# DasAltimeter_v1_1.net
KiCad netlist of a schematic drawn in EAGLE
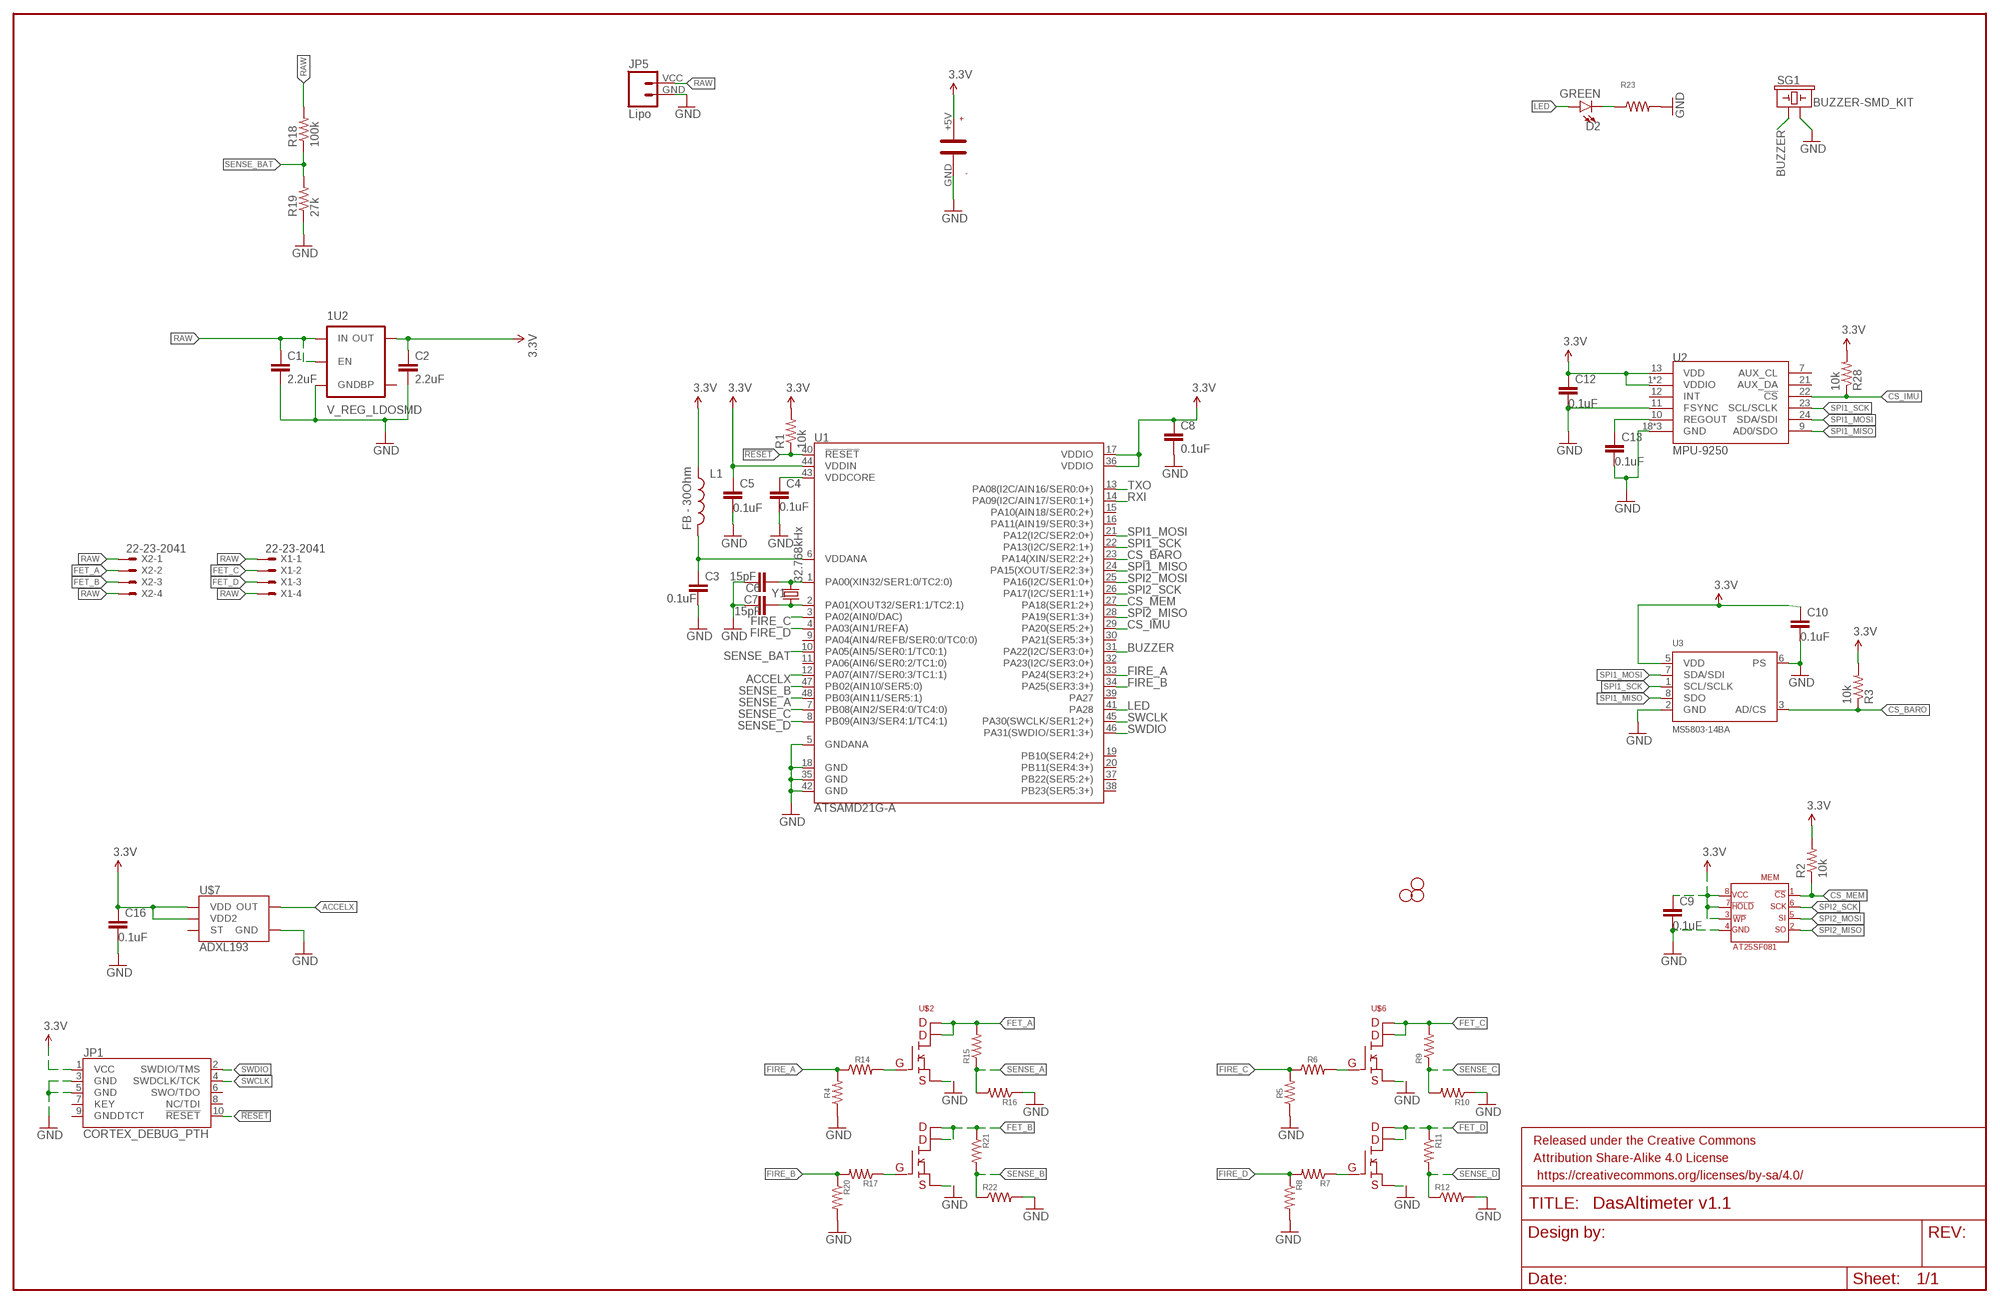
[diagram p0: schematic, sheet 1]

(export (version "E")
  (design (tool "Eeschema 10.0.6"))
  (components
    (comp (ref "1U2")
      (value "V_REG_LDOSMD")
      (footprint "eagle-import:SOT23-5")
      (libsource (lib "eagle-import") (part "V_REG_LDOSMD"))
    )
    (comp (ref "C1")
      (value "2.2uF")
      (footprint "eagle-import:0603-CAP")
      (libsource (lib "eagle-import") (part "CAP0603-CAP"))
    )
    (comp (ref "C2")
      (value "2.2uF")
      (footprint "eagle-import:0603-CAP")
      (libsource (lib "eagle-import") (part "CAP0603-CAP"))
    )
    (comp (ref "C3")
      (value "0.1uF")
      (footprint "eagle-import:0402-CAP")
      (libsource (lib "eagle-import") (part "SparkFun-Passives_CAP0402-CAP"))
    )
    (comp (ref "C4")
      (value "0.1uF")
      (footprint "eagle-import:0402-CAP")
      (libsource (lib "eagle-import") (part "SparkFun-Passives_CAP0402-CAP"))
    )
    (comp (ref "C5")
      (value "0.1uF")
      (footprint "eagle-import:0402-CAP")
      (libsource (lib "eagle-import") (part "SparkFun-Passives_CAP0402-CAP"))
    )
    (comp (ref "C6")
      (value "15pF")
      (footprint "eagle-import:0402-CAP")
      (libsource (lib "eagle-import") (part "SparkFun-Passives_CAP0402-CAP"))
    )
    (comp (ref "C7")
      (value "15pF")
      (footprint "eagle-import:0402-CAP")
      (libsource (lib "eagle-import") (part "SparkFun-Passives_CAP0402-CAP"))
    )
    (comp (ref "C8")
      (value "0.1uF")
      (footprint "eagle-import:0402-CAP")
      (libsource (lib "eagle-import") (part "SparkFun-Passives_CAP0402-CAP"))
    )
    (comp (ref "C9")
      (value "0.1uF")
      (footprint "eagle-import:0402-CAP")
      (libsource (lib "eagle-import") (part "SparkFun-Passives_CAP0402-CAP"))
    )
    (comp (ref "C10")
      (value "0.1uF")
      (footprint "eagle-import:0402-CAP")
      (libsource (lib "eagle-import") (part "SparkFun-Passives_CAP0402-CAP"))
    )
    (comp (ref "C12")
      (value "0.1uF")
      (footprint "eagle-import:0402-CAP")
      (libsource (lib "eagle-import") (part "SparkFun-Passives_CAP0402-CAP"))
    )
    (comp (ref "C13")
      (value "0.1uF")
      (footprint "eagle-import:0402-CAP")
      (libsource (lib "eagle-import") (part "SparkFun-Passives_CAP0402-CAP"))
    )
    (comp (ref "C16")
      (value "0.1uF")
      (footprint "eagle-import:0402-CAP")
      (libsource (lib "eagle-import") (part "SparkFun-Passives_CAP0402-CAP"))
    )
    (comp (ref "D2")
      (value "GREEN")
      (footprint "eagle-import:LED-1206")
      (libsource (lib "eagle-import") (part "LED-GREEN1206"))
    )
    (comp (ref "FRAME1")
      (value "FRAME-LEDGER")
      (footprint "eagle-import:CREATIVE_COMMONS")
      (libsource (lib "eagle-import") (part "FRAME-LEDGER"))
    )
    (comp (ref "JP1")
      (value "CORTEX_DEBUG_PTH")
      (footprint "eagle-import:2X5-PTH-1.27MM")
      (libsource (lib "eagle-import") (part "CORTEX_DEBUG_PTH"))
    )
    (comp (ref "JP5")
      (value "Lipo")
      (footprint "eagle-import:JST-2-SMD-VERT")
      (libsource (lib "eagle-import") (part "M024UCON-15767"))
    )
    (comp (ref "L1")
      (value "FB - 30Ohm")
      (footprint "eagle-import:0603")
      (libsource (lib "eagle-import") (part "INDUCTOR0603"))
    )
    (comp (ref "MEM")
      (value "AT25SF081")
      (footprint "eagle-import:AT25SF081")
      (libsource (lib "eagle-import") (part "AT25SF081"))
    )
    (comp (ref "R1")
      (value "10k")
      (footprint "eagle-import:0402-RES")
      (libsource (lib "eagle-import") (part "RESISTOR0402-RES"))
    )
    (comp (ref "R2")
      (value "10k")
      (footprint "eagle-import:0402-RES")
      (libsource (lib "eagle-import") (part "RESISTOR0402-RES"))
    )
    (comp (ref "R3")
      (value "10k")
      (footprint "eagle-import:0402-RES")
      (libsource (lib "eagle-import") (part "RESISTOR0402-RES"))
    )
    (comp (ref "R4")
      (value "RESISTOR0402")
      (footprint "eagle-import:0402")
      (libsource (lib "eagle-import") (part "RESISTOR0402"))
    )
    (comp (ref "R5")
      (value "RESISTOR0402")
      (footprint "eagle-import:0402")
      (libsource (lib "eagle-import") (part "RESISTOR0402"))
    )
    (comp (ref "R6")
      (value "RESISTOR0402")
      (footprint "eagle-import:0402")
      (libsource (lib "eagle-import") (part "RESISTOR0402"))
    )
    (comp (ref "R7")
      (value "RESISTOR0402")
      (footprint "eagle-import:0402")
      (libsource (lib "eagle-import") (part "RESISTOR0402"))
    )
    (comp (ref "R8")
      (value "RESISTOR0402")
      (footprint "eagle-import:0402")
      (libsource (lib "eagle-import") (part "RESISTOR0402"))
    )
    (comp (ref "R9")
      (value "RESISTOR0402")
      (footprint "eagle-import:0402")
      (libsource (lib "eagle-import") (part "RESISTOR0402"))
    )
    (comp (ref "R10")
      (value "RESISTOR0402")
      (footprint "eagle-import:0402")
      (libsource (lib "eagle-import") (part "RESISTOR0402"))
    )
    (comp (ref "R11")
      (value "RESISTOR0402")
      (footprint "eagle-import:0402")
      (libsource (lib "eagle-import") (part "RESISTOR0402"))
    )
    (comp (ref "R12")
      (value "RESISTOR0402")
      (footprint "eagle-import:0402")
      (libsource (lib "eagle-import") (part "RESISTOR0402"))
    )
    (comp (ref "R14")
      (value "RESISTOR0402")
      (footprint "eagle-import:0402")
      (libsource (lib "eagle-import") (part "RESISTOR0402"))
    )
    (comp (ref "R15")
      (value "RESISTOR0402")
      (footprint "eagle-import:0402")
      (libsource (lib "eagle-import") (part "RESISTOR0402"))
    )
    (comp (ref "R16")
      (value "RESISTOR0402")
      (footprint "eagle-import:0402")
      (libsource (lib "eagle-import") (part "RESISTOR0402"))
    )
    (comp (ref "R17")
      (value "RESISTOR0402")
      (footprint "eagle-import:0402")
      (libsource (lib "eagle-import") (part "RESISTOR0402"))
    )
    (comp (ref "R18")
      (value "100k")
      (footprint "eagle-import:0402-RES")
      (libsource (lib "eagle-import") (part "RESISTOR0402-RES"))
    )
    (comp (ref "R19")
      (value "27k")
      (footprint "eagle-import:0402-RES")
      (libsource (lib "eagle-import") (part "RESISTOR0402-RES"))
    )
    (comp (ref "R20")
      (value "RESISTOR0402")
      (footprint "eagle-import:0402")
      (libsource (lib "eagle-import") (part "RESISTOR0402"))
    )
    (comp (ref "R21")
      (value "RESISTOR0402")
      (footprint "eagle-import:0402")
      (libsource (lib "eagle-import") (part "RESISTOR0402"))
    )
    (comp (ref "R22")
      (value "RESISTOR0402")
      (footprint "eagle-import:0402")
      (libsource (lib "eagle-import") (part "RESISTOR0402"))
    )
    (comp (ref "R23")
      (value "RESISTOR0402")
      (footprint "eagle-import:0402")
      (libsource (lib "eagle-import") (part "RESISTOR0402"))
    )
    (comp (ref "R28")
      (value "10k")
      (footprint "eagle-import:0402-RES")
      (libsource (lib "eagle-import") (part "RESISTOR0402-RES"))
    )
    (comp (ref "SG1")
      (value "BUZZER-SMD_KIT")
      (footprint "eagle-import:BUZZER-CCV-KIT")
      (libsource (lib "eagle-import") (part "BUZZER-SMD_KIT"))
    )
    (comp (ref "STANDOFF2")
      (value "STAND-OFF")
      (footprint "eagle-import:STAND-OFF")
      (libsource (lib "eagle-import") (part "STAND-OFF"))
    )
    (comp (ref "STANDOFF3")
      (value "STAND-OFF")
      (footprint "eagle-import:STAND-OFF")
      (libsource (lib "eagle-import") (part "STAND-OFF"))
    )
    (comp (ref "STANDOFF4")
      (value "STAND-OFF")
      (footprint "eagle-import:STAND-OFF")
      (libsource (lib "eagle-import") (part "STAND-OFF"))
    )
    (comp (ref "U$1")
      (value "PB-5R0H104-R")
      (footprint "eagle-import:PB-5R0H104-R")
      (libsource (lib "eagle-import") (part "PB-5R0H104-R"))
    )
    (comp (ref "U$2")
      (value "SI7232DN")
      (footprint "eagle-import:SI7232DN")
      (libsource (lib "eagle-import") (part "SI7232DN"))
    )
    (comp (ref "U$6")
      (value "SI7232DN")
      (footprint "eagle-import:SI7232DN")
      (libsource (lib "eagle-import") (part "SI7232DN"))
    )
    (comp (ref "U$7")
      (value "ADXL193")
      (footprint "eagle-import:LCC-8")
      (libsource (lib "eagle-import") (part "ADXL193"))
    )
    (comp (ref "U1")
      (value "ATSAMD21G-A")
      (footprint "eagle-import:TQFP-48")
      (libsource (lib "eagle-import") (part "ATSAMD21G-A"))
    )
    (comp (ref "U2")
      (value "MPU-9250")
      (footprint "eagle-import:QFN24_PAD")
      (libsource (lib "eagle-import") (part "MPU-9250"))
    )
    (comp (ref "U3")
      (value "MS5803-14BA")
      (footprint "eagle-import:MS5803")
      (libsource (lib "eagle-import") (part "MS5803-14BA"))
    )
    (comp (ref "X1")
      (value "22-23-2041")
      (footprint "eagle-import:22-23-2041")
      (fields (field (name "MF") "MOLEX"))
      (libsource (lib "eagle-import") (part "22-23-2041"))
    )
    (comp (ref "X2")
      (value "22-23-2041")
      (footprint "eagle-import:22-23-2041")
      (fields (field (name "MF") "MOLEX"))
      (libsource (lib "eagle-import") (part "22-23-2041"))
    )
    (comp (ref "Y1")
      (value "32.768kHx")
      (footprint "eagle-import:CRYSTAL-SMD-3.2X1.5MM")
      (libsource (lib "eagle-import") (part "CRYSTAL3.2X1.5MM"))
    )
  )
  (nets
    (net (code "1") (name "/BUZZER") (class "Default")
      (node (ref "SG1") (pin "+") (pinfunction "1_+") (pintype "passive"))
      (node (ref "U1") (pin "31") (pinfunction "PA22(I2C/SER3:0+)_31") (pintype "bidirectional"))
    )
    (net (code "2") (name "/RXI") (class "Default")
      (node (ref "U1") (pin "14") (pinfunction "PA09(I2C/AIN17/SER0:1+)_14") (pintype "bidirectional"))
    )
    (net (code "3") (name "/TXO") (class "Default")
      (node (ref "U1") (pin "13") (pinfunction "PA08(I2C/AIN16/SER0:0+)_13") (pintype "bidirectional"))
    )
    (net (code "4") (name "/~{RESET}") (class "Default")
      (node (ref "JP1") (pin "10") (pinfunction "~{RESET}_10") (pintype "bidirectional"))
      (node (ref "R1") (pin "1") (pinfunction "1_1") (pintype "passive"))
      (node (ref "U1") (pin "40") (pinfunction "~{RESET}_40") (pintype "bidirectional"))
    )
    (net (code "5") (name "3.3V") (class "Default")
      (node (ref "1U2") (pin "5") (pinfunction "OUT_5") (pintype "passive"))
      (node (ref "C10") (pin "1") (pinfunction "1_1") (pintype "passive"))
      (node (ref "C12") (pin "1") (pinfunction "1_1") (pintype "passive"))
      (node (ref "C16") (pin "1") (pinfunction "1_1") (pintype "passive"))
      (node (ref "C2") (pin "1") (pinfunction "1_1") (pintype "passive"))
      (node (ref "C5") (pin "1") (pinfunction "1_1") (pintype "passive"))
      (node (ref "C8") (pin "1") (pinfunction "1_1") (pintype "passive"))
      (node (ref "C9") (pin "1") (pinfunction "1_1") (pintype "passive"))
      (node (ref "JP1") (pin "1") (pinfunction "VCC_1") (pintype "bidirectional"))
      (node (ref "L1") (pin "1") (pinfunction "1_1") (pintype "passive"))
      (node (ref "MEM") (pin "!HOLD") (pinfunction "~{HOLD}_!HOLD") (pintype "bidirectional"))
      (node (ref "MEM") (pin "!WP") (pinfunction "~{WP}_!WP") (pintype "bidirectional"))
      (node (ref "MEM") (pin "VCC") (pinfunction "VCC_VCC") (pintype "bidirectional"))
      (node (ref "R1") (pin "2") (pinfunction "2_2") (pintype "passive"))
      (node (ref "R2") (pin "2") (pinfunction "2_2") (pintype "passive"))
      (node (ref "R28") (pin "2") (pinfunction "2_2") (pintype "passive"))
      (node (ref "R3") (pin "2") (pinfunction "2_2") (pintype "passive"))
      (node (ref "U$1") (pin "+5V") (pinfunction "+5V_+5V") (pintype "bidirectional"))
      (node (ref "U$7") (pin "P$7") (pinfunction "VDD_P$7") (pintype "bidirectional"))
      (node (ref "U$7") (pin "P$8") (pinfunction "VDD2_P$8") (pintype "bidirectional"))
      (node (ref "U1") (pin "17") (pinfunction "VDDIO_17") (pintype "bidirectional"))
      (node (ref "U1") (pin "36") (pinfunction "VDDIO_36") (pintype "bidirectional"))
      (node (ref "U1") (pin "44") (pinfunction "VDDIN_44") (pintype "bidirectional"))
      (node (ref "U2") (pin "1") (pinfunction "VDDIO_1") (pintype "bidirectional"))
      (node (ref "U2") (pin "13") (pinfunction "VDD_13") (pintype "bidirectional"))
      (node (ref "U2") (pin "8") (pinfunction "VDDIO_8") (pintype "bidirectional"))
      (node (ref "U3") (pin "5") (pinfunction "VDD_5") (pintype "bidirectional"))
    )
    (net (code "6") (name "ACCELX") (class "Default")
      (node (ref "U$7") (pin "P$6") (pinfunction "OUT_P$6") (pintype "bidirectional"))
      (node (ref "U1") (pin "12") (pinfunction "PA07(AIN7/SER0:3/TC1:1)_12") (pintype "bidirectional"))
    )
    (net (code "7") (name "CS_BARO") (class "Default")
      (node (ref "R3") (pin "1") (pinfunction "1_1") (pintype "passive"))
      (node (ref "U1") (pin "23") (pinfunction "PA14(XIN/SER2:2+)_23") (pintype "bidirectional"))
      (node (ref "U3") (pin "3") (pinfunction "AD/CS_3") (pintype "bidirectional"))
    )
    (net (code "8") (name "CS_IMU") (class "Default")
      (node (ref "R28") (pin "1") (pinfunction "1_1") (pintype "passive"))
      (node (ref "U1") (pin "29") (pinfunction "PA20(SER5:2+)_29") (pintype "bidirectional"))
      (node (ref "U2") (pin "22") (pinfunction "~{CS}_22") (pintype "bidirectional"))
    )
    (net (code "9") (name "CS_MEM") (class "Default")
      (node (ref "MEM") (pin "!CS") (pinfunction "~{CS}_!CS") (pintype "bidirectional"))
      (node (ref "R2") (pin "1") (pinfunction "1_1") (pintype "passive"))
      (node (ref "U1") (pin "27") (pinfunction "PA18(SER1:2+)_27") (pintype "bidirectional"))
    )
    (net (code "10") (name "FET_A") (class "Default")
      (node (ref "R15") (pin "2") (pinfunction "2_2") (pintype "passive"))
      (node (ref "U$2") (pin "7") (pinfunction "PIN7_7") (pintype "bidirectional"))
      (node (ref "U$2") (pin "8") (pinfunction "PIN8_8") (pintype "bidirectional"))
      (node (ref "X2") (pin "2") (pinfunction "S_2") (pintype "passive"))
    )
    (net (code "11") (name "FET_B") (class "Default")
      (node (ref "R21") (pin "1") (pinfunction "1_1") (pintype "passive"))
      (node (ref "U$2") (pin "5") (pinfunction "PIN5_5") (pintype "bidirectional"))
      (node (ref "U$2") (pin "6") (pinfunction "PIN6_6") (pintype "bidirectional"))
      (node (ref "X2") (pin "3") (pinfunction "S_3") (pintype "passive"))
    )
    (net (code "12") (name "FET_C") (class "Default")
      (node (ref "R9") (pin "2") (pinfunction "2_2") (pintype "passive"))
      (node (ref "U$6") (pin "7") (pinfunction "PIN7_7") (pintype "bidirectional"))
      (node (ref "U$6") (pin "8") (pinfunction "PIN8_8") (pintype "bidirectional"))
      (node (ref "X1") (pin "2") (pinfunction "S_2") (pintype "passive"))
    )
    (net (code "13") (name "FET_D") (class "Default")
      (node (ref "R11") (pin "1") (pinfunction "1_1") (pintype "passive"))
      (node (ref "U$6") (pin "5") (pinfunction "PIN5_5") (pintype "bidirectional"))
      (node (ref "U$6") (pin "6") (pinfunction "PIN6_6") (pintype "bidirectional"))
      (node (ref "X1") (pin "3") (pinfunction "S_3") (pintype "passive"))
    )
    (net (code "14") (name "FIRE_A") (class "Default")
      (node (ref "R14") (pin "1") (pinfunction "1_1") (pintype "passive"))
      (node (ref "R4") (pin "2") (pinfunction "2_2") (pintype "passive"))
      (node (ref "U1") (pin "33") (pinfunction "PA24(SER3:2+)_33") (pintype "bidirectional"))
    )
    (net (code "15") (name "FIRE_B") (class "Default")
      (node (ref "R17") (pin "2") (pinfunction "2_2") (pintype "passive"))
      (node (ref "R20") (pin "1") (pinfunction "1_1") (pintype "passive"))
      (node (ref "U1") (pin "34") (pinfunction "PA25(SER3:3+)_34") (pintype "bidirectional"))
    )
    (net (code "16") (name "FIRE_C") (class "Default")
      (node (ref "R5") (pin "2") (pinfunction "2_2") (pintype "passive"))
      (node (ref "R6") (pin "1") (pinfunction "1_1") (pintype "passive"))
      (node (ref "U1") (pin "3") (pinfunction "PA02(AIN0/DAC)_3") (pintype "bidirectional"))
    )
    (net (code "17") (name "FIRE_D") (class "Default")
      (node (ref "R7") (pin "2") (pinfunction "2_2") (pintype "passive"))
      (node (ref "R8") (pin "1") (pinfunction "1_1") (pintype "passive"))
      (node (ref "U1") (pin "4") (pinfunction "PA03(AIN1/REFA)_4") (pintype "bidirectional"))
    )
    (net (code "18") (name "GND") (class "Default")
      (node (ref "1U2") (pin "2") (pinfunction "GND_2") (pintype "input"))
      (node (ref "C1") (pin "2") (pinfunction "2_2") (pintype "passive"))
      (node (ref "C10") (pin "2") (pinfunction "2_2") (pintype "passive"))
      (node (ref "C12") (pin "2") (pinfunction "2_2") (pintype "passive"))
      (node (ref "C13") (pin "2") (pinfunction "2_2") (pintype "passive"))
      (node (ref "C16") (pin "2") (pinfunction "2_2") (pintype "passive"))
      (node (ref "C2") (pin "2") (pinfunction "2_2") (pintype "passive"))
      (node (ref "C3") (pin "2") (pinfunction "2_2") (pintype "passive"))
      (node (ref "C4") (pin "2") (pinfunction "2_2") (pintype "passive"))
      (node (ref "C5") (pin "2") (pinfunction "2_2") (pintype "passive"))
      (node (ref "C6") (pin "2") (pinfunction "2_2") (pintype "passive"))
      (node (ref "C7") (pin "2") (pinfunction "2_2") (pintype "passive"))
      (node (ref "C8") (pin "2") (pinfunction "2_2") (pintype "passive"))
      (node (ref "C9") (pin "2") (pinfunction "2_2") (pintype "passive"))
      (node (ref "JP1") (pin "3") (pinfunction "GND_3") (pintype "bidirectional"))
      (node (ref "JP1") (pin "5") (pinfunction "GND_5") (pintype "bidirectional"))
      (node (ref "JP5") (pin "GND") (pinfunction "1_GND") (pintype "passive"))
      (node (ref "MEM") (pin "GND") (pinfunction "GND_GND") (pintype "bidirectional"))
      (node (ref "R10") (pin "1") (pinfunction "1_1") (pintype "passive"))
      (node (ref "R12") (pin "2") (pinfunction "2_2") (pintype "passive"))
      (node (ref "R16") (pin "1") (pinfunction "1_1") (pintype "passive"))
      (node (ref "R19") (pin "1") (pinfunction "1_1") (pintype "passive"))
      (node (ref "R20") (pin "2") (pinfunction "2_2") (pintype "passive"))
      (node (ref "R22") (pin "2") (pinfunction "2_2") (pintype "passive"))
      (node (ref "R23") (pin "2") (pinfunction "2_2") (pintype "passive"))
      (node (ref "R4") (pin "1") (pinfunction "1_1") (pintype "passive"))
      (node (ref "R5") (pin "1") (pinfunction "1_1") (pintype "passive"))
      (node (ref "R8") (pin "2") (pinfunction "2_2") (pintype "passive"))
      (node (ref "SG1") (pin "-") (pinfunction "2_-") (pintype "passive"))
      (node (ref "U$1") (pin "GND") (pinfunction "GND_GND") (pintype "bidirectional"))
      (node (ref "U$2") (pin "1") (pinfunction "PIN1_1") (pintype "bidirectional"))
      (node (ref "U$2") (pin "3") (pinfunction "PIN3_3") (pintype "bidirectional"))
      (node (ref "U$6") (pin "1") (pinfunction "PIN1_1") (pintype "bidirectional"))
      (node (ref "U$6") (pin "3") (pinfunction "PIN3_3") (pintype "bidirectional"))
      (node (ref "U$7") (pin "P$3") (pinfunction "GND_P$3") (pintype "bidirectional"))
      (node (ref "U1") (pin "18") (pinfunction "GND_18") (pintype "bidirectional"))
      (node (ref "U1") (pin "35") (pinfunction "GND_35") (pintype "bidirectional"))
      (node (ref "U1") (pin "42") (pinfunction "GND_42") (pintype "bidirectional"))
      (node (ref "U1") (pin "5") (pinfunction "GNDANA_5") (pintype "bidirectional"))
      (node (ref "U2") (pin "11") (pinfunction "FSYNC_11") (pintype "bidirectional"))
      (node (ref "U2") (pin "18") (pinfunction "GND_18") (pintype "bidirectional"))
      (node (ref "U2") (pin "20") (pinfunction "GND_20") (pintype "bidirectional"))
      (node (ref "U2") (pin "CENTER") (pinfunction "GND_CENTER") (pintype "bidirectional"))
      (node (ref "U3") (pin "2") (pinfunction "GND_2") (pintype "bidirectional"))
      (node (ref "U3") (pin "6") (pinfunction "PS_6") (pintype "bidirectional"))
    )
    (net (code "19") (name "LED") (class "Default")
      (node (ref "D2") (pin "A") (pinfunction "A_A") (pintype "passive"))
      (node (ref "U1") (pin "41") (pinfunction "PA28_41") (pintype "bidirectional"))
    )
    (net (code "20") (name "Net-(D2-PadC)") (class "Default")
      (node (ref "D2") (pin "C") (pinfunction "C_C") (pintype "passive"))
      (node (ref "R23") (pin "1") (pinfunction "1_1") (pintype "passive"))
    )
    (net (code "21") (name "Net-(U$2-PIN2)") (class "Default")
      (node (ref "R14") (pin "2") (pinfunction "2_2") (pintype "passive"))
      (node (ref "U$2") (pin "2") (pinfunction "PIN2_2") (pintype "bidirectional"))
    )
    (net (code "22") (name "Net-(U$2-PIN4)") (class "Default")
      (node (ref "R17") (pin "1") (pinfunction "1_1") (pintype "passive"))
      (node (ref "U$2") (pin "4") (pinfunction "PIN4_4") (pintype "bidirectional"))
    )
    (net (code "23") (name "Net-(U$6-PIN2)") (class "Default")
      (node (ref "R6") (pin "2") (pinfunction "2_2") (pintype "passive"))
      (node (ref "U$6") (pin "2") (pinfunction "PIN2_2") (pintype "bidirectional"))
    )
    (net (code "24") (name "Net-(U$6-PIN4)") (class "Default")
      (node (ref "R7") (pin "1") (pinfunction "1_1") (pintype "passive"))
      (node (ref "U$6") (pin "4") (pinfunction "PIN4_4") (pintype "bidirectional"))
    )
    (net (code "25") (name "Net-(U1-PA00(XIN32{slash}SER1:0{slash}TC2:0))") (class "Default")
      (node (ref "C6") (pin "1") (pinfunction "1_1") (pintype "passive"))
      (node (ref "U1") (pin "1") (pinfunction "PA00(XIN32/SER1:0/TC2:0)_1") (pintype "bidirectional"))
      (node (ref "Y1") (pin "P$2") (pinfunction "2_P$2") (pintype "passive"))
    )
    (net (code "26") (name "Net-(U1-PA01(XOUT32{slash}SER1:1{slash}TC2:1))") (class "Default")
      (node (ref "C7") (pin "1") (pinfunction "1_1") (pintype "passive"))
      (node (ref "U1") (pin "2") (pinfunction "PA01(XOUT32/SER1:1/TC2:1)_2") (pintype "bidirectional"))
      (node (ref "Y1") (pin "P$1") (pinfunction "1_P$1") (pintype "passive"))
    )
    (net (code "27") (name "Net-(U1-VDDANA)") (class "Default")
      (node (ref "C3") (pin "1") (pinfunction "1_1") (pintype "passive"))
      (node (ref "L1") (pin "2") (pinfunction "2_2") (pintype "passive"))
      (node (ref "U1") (pin "6") (pinfunction "VDDANA_6") (pintype "bidirectional"))
    )
    (net (code "28") (name "Net-(U1-VDDCORE)") (class "Default")
      (node (ref "C4") (pin "1") (pinfunction "1_1") (pintype "passive"))
      (node (ref "U1") (pin "43") (pinfunction "VDDCORE_43") (pintype "bidirectional"))
    )
    (net (code "29") (name "Net-(U2-REGOUT)") (class "Default")
      (node (ref "C13") (pin "1") (pinfunction "1_1") (pintype "passive"))
      (node (ref "U2") (pin "10") (pinfunction "REGOUT_10") (pintype "bidirectional"))
    )
    (net (code "30") (name "RAW") (class "Default")
      (node (ref "1U2") (pin "1") (pinfunction "IN_1") (pintype "input"))
      (node (ref "1U2") (pin "3") (pinfunction "EN_3") (pintype "input"))
      (node (ref "C1") (pin "1") (pinfunction "1_1") (pintype "passive"))
      (node (ref "JP5") (pin "VCC") (pinfunction "2_VCC") (pintype "passive"))
      (node (ref "R18") (pin "2") (pinfunction "2_2") (pintype "passive"))
      (node (ref "X1") (pin "1") (pinfunction "S_1") (pintype "passive"))
      (node (ref "X1") (pin "4") (pinfunction "S_4") (pintype "passive"))
      (node (ref "X2") (pin "1") (pinfunction "S_1") (pintype "passive"))
      (node (ref "X2") (pin "4") (pinfunction "S_4") (pintype "passive"))
    )
    (net (code "31") (name "SENSE_A") (class "Default")
      (node (ref "R15") (pin "1") (pinfunction "1_1") (pintype "passive"))
      (node (ref "R16") (pin "2") (pinfunction "2_2") (pintype "passive"))
      (node (ref "U1") (pin "48") (pinfunction "PB03(AIN11/SER5:1)_48") (pintype "bidirectional"))
    )
    (net (code "32") (name "SENSE_B") (class "Default")
      (node (ref "R21") (pin "2") (pinfunction "2_2") (pintype "passive"))
      (node (ref "R22") (pin "1") (pinfunction "1_1") (pintype "passive"))
      (node (ref "U1") (pin "47") (pinfunction "PB02(AIN10/SER5:0)_47") (pintype "bidirectional"))
    )
    (net (code "33") (name "SENSE_BAT") (class "Default")
      (node (ref "R18") (pin "1") (pinfunction "1_1") (pintype "passive"))
      (node (ref "R19") (pin "2") (pinfunction "2_2") (pintype "passive"))
      (node (ref "U1") (pin "10") (pinfunction "PA05(AIN5/SER0:1/TC0:1)_10") (pintype "bidirectional"))
    )
    (net (code "34") (name "SENSE_C") (class "Default")
      (node (ref "R10") (pin "2") (pinfunction "2_2") (pintype "passive"))
      (node (ref "R9") (pin "1") (pinfunction "1_1") (pintype "passive"))
      (node (ref "U1") (pin "7") (pinfunction "PB08(AIN2/SER4:0/TC4:0)_7") (pintype "bidirectional"))
    )
    (net (code "35") (name "SENSE_D") (class "Default")
      (node (ref "R11") (pin "2") (pinfunction "2_2") (pintype "passive"))
      (node (ref "R12") (pin "1") (pinfunction "1_1") (pintype "passive"))
      (node (ref "U1") (pin "8") (pinfunction "PB09(AIN3/SER4:1/TC4:1)_8") (pintype "bidirectional"))
    )
    (net (code "36") (name "SPI1_MISO") (class "Default")
      (node (ref "U1") (pin "24") (pinfunction "PA15(XOUT/SER2:3+)_24") (pintype "bidirectional"))
      (node (ref "U2") (pin "9") (pinfunction "AD0/SDO_9") (pintype "bidirectional"))
      (node (ref "U3") (pin "8") (pinfunction "SDO_8") (pintype "bidirectional"))
    )
    (net (code "37") (name "SPI1_MOSI") (class "Default")
      (node (ref "U1") (pin "21") (pinfunction "PA12(I2C/SER2:0+)_21") (pintype "bidirectional"))
      (node (ref "U2") (pin "24") (pinfunction "SDA/SDI_24") (pintype "bidirectional"))
      (node (ref "U3") (pin "7") (pinfunction "SDA/SDI_7") (pintype "bidirectional"))
    )
    (net (code "38") (name "SPI1_SCK") (class "Default")
      (node (ref "U1") (pin "22") (pinfunction "PA13(I2C/SER2:1+)_22") (pintype "bidirectional"))
      (node (ref "U2") (pin "23") (pinfunction "SCL/SCLK_23") (pintype "bidirectional"))
      (node (ref "U3") (pin "1") (pinfunction "SCL/SCLK_1") (pintype "bidirectional"))
    )
    (net (code "39") (name "SPI2_MISO") (class "Default")
      (node (ref "MEM") (pin "SO") (pinfunction "SO_SO") (pintype "bidirectional"))
      (node (ref "U1") (pin "28") (pinfunction "PA19(SER1:3+)_28") (pintype "bidirectional"))
    )
    (net (code "40") (name "SPI2_MOSI") (class "Default")
      (node (ref "MEM") (pin "SI") (pinfunction "SI_SI") (pintype "bidirectional"))
      (node (ref "U1") (pin "25") (pinfunction "PA16(I2C/SER1:0+)_25") (pintype "bidirectional"))
    )
    (net (code "41") (name "SPI2_SCK") (class "Default")
      (node (ref "MEM") (pin "SCK") (pinfunction "SCK_SCK") (pintype "bidirectional"))
      (node (ref "U1") (pin "26") (pinfunction "PA17(I2C/SER1:1+)_26") (pintype "bidirectional"))
    )
    (net (code "42") (name "SWCLK") (class "Default")
      (node (ref "JP1") (pin "4") (pinfunction "SWDCLK/TCK_4") (pintype "bidirectional"))
      (node (ref "U1") (pin "45") (pinfunction "PA30(SWCLK/SER1:2+)_45") (pintype "bidirectional"))
    )
    (net (code "43") (name "SWDIO") (class "Default")
      (node (ref "JP1") (pin "2") (pinfunction "SWDIO/TMS_2") (pintype "bidirectional"))
      (node (ref "U1") (pin "46") (pinfunction "PA31(SWDIO/SER1:3+)_46") (pintype "bidirectional"))
    )
    (net (code "44") (name "unconnected-(1U2-BP-Pad4)") (class "Default")
      (node (ref "1U2") (pin "4") (pinfunction "BP_4") (pintype "input"))
    )
    (net (code "45") (name "unconnected-(JP1-GNDDTCT-Pad9)") (class "Default")
      (node (ref "JP1") (pin "9") (pinfunction "GNDDTCT_9") (pintype "bidirectional"))
    )
    (net (code "46") (name "unconnected-(JP1-KEY-Pad7)") (class "Default")
      (node (ref "JP1") (pin "7") (pinfunction "KEY_7") (pintype "bidirectional"))
    )
    (net (code "47") (name "unconnected-(JP1-NC{slash}TDI-Pad8)") (class "Default")
      (node (ref "JP1") (pin "8") (pinfunction "NC/TDI_8") (pintype "bidirectional"))
    )
    (net (code "48") (name "unconnected-(JP1-SWO{slash}TDO-Pad6)") (class "Default")
      (node (ref "JP1") (pin "6") (pinfunction "SWO/TDO_6") (pintype "bidirectional"))
    )
    (net (code "49") (name "unconnected-(U$7-ST-PadP$4)") (class "Default")
      (node (ref "U$7") (pin "P$4") (pinfunction "ST_P$4") (pintype "bidirectional"))
    )
    (net (code "50") (name "unconnected-(U1-PA04(AIN4{slash}REFB{slash}SER0:0{slash}TC0:0)-Pad9)") (class "Default")
      (node (ref "U1") (pin "9") (pinfunction "PA04(AIN4/REFB/SER0:0/TC0:0)_9") (pintype "bidirectional"))
    )
    (net (code "51") (name "unconnected-(U1-PA06(AIN6{slash}SER0:2{slash}TC1:0)-Pad11)") (class "Default")
      (node (ref "U1") (pin "11") (pinfunction "PA06(AIN6/SER0:2/TC1:0)_11") (pintype "bidirectional"))
    )
    (net (code "52") (name "unconnected-(U1-PA10(AIN18{slash}SER0:2+)-Pad15)") (class "Default")
      (node (ref "U1") (pin "15") (pinfunction "PA10(AIN18/SER0:2+)_15") (pintype "bidirectional"))
    )
    (net (code "53") (name "unconnected-(U1-PA11(AIN19{slash}SER0:3+)-Pad16)") (class "Default")
      (node (ref "U1") (pin "16") (pinfunction "PA11(AIN19/SER0:3+)_16") (pintype "bidirectional"))
    )
    (net (code "54") (name "unconnected-(U1-PA21(SER5:3+)-Pad30)") (class "Default")
      (node (ref "U1") (pin "30") (pinfunction "PA21(SER5:3+)_30") (pintype "bidirectional"))
    )
    (net (code "55") (name "unconnected-(U1-PA23(I2C{slash}SER3:0+)-Pad32)") (class "Default")
      (node (ref "U1") (pin "32") (pinfunction "PA23(I2C/SER3:0+)_32") (pintype "bidirectional"))
    )
    (net (code "56") (name "unconnected-(U1-PA27-Pad39)") (class "Default")
      (node (ref "U1") (pin "39") (pinfunction "PA27_39") (pintype "bidirectional"))
    )
    (net (code "57") (name "unconnected-(U1-PB10(SER4:2+)-Pad19)") (class "Default")
      (node (ref "U1") (pin "19") (pinfunction "PB10(SER4:2+)_19") (pintype "bidirectional"))
    )
    (net (code "58") (name "unconnected-(U1-PB11(SER4:3+)-Pad20)") (class "Default")
      (node (ref "U1") (pin "20") (pinfunction "PB11(SER4:3+)_20") (pintype "bidirectional"))
    )
    (net (code "59") (name "unconnected-(U1-PB22(SER5:2+)-Pad37)") (class "Default")
      (node (ref "U1") (pin "37") (pinfunction "PB22(SER5:2+)_37") (pintype "bidirectional"))
    )
    (net (code "60") (name "unconnected-(U1-PB23(SER5:3+)-Pad38)") (class "Default")
      (node (ref "U1") (pin "38") (pinfunction "PB23(SER5:3+)_38") (pintype "bidirectional"))
    )
    (net (code "61") (name "unconnected-(U2-AUX_CL-Pad7)") (class "Default")
      (node (ref "U2") (pin "7") (pinfunction "AUX_CL_7") (pintype "bidirectional"))
    )
    (net (code "62") (name "unconnected-(U2-AUX_DA-Pad21)") (class "Default")
      (node (ref "U2") (pin "21") (pinfunction "AUX_DA_21") (pintype "bidirectional"))
    )
    (net (code "63") (name "unconnected-(U2-INT-Pad12)") (class "Default")
      (node (ref "U2") (pin "12") (pinfunction "INT_12") (pintype "bidirectional"))
    )
  )
)
